# Power.net
KiCad netlist of a schematic drawn in Altium Designer
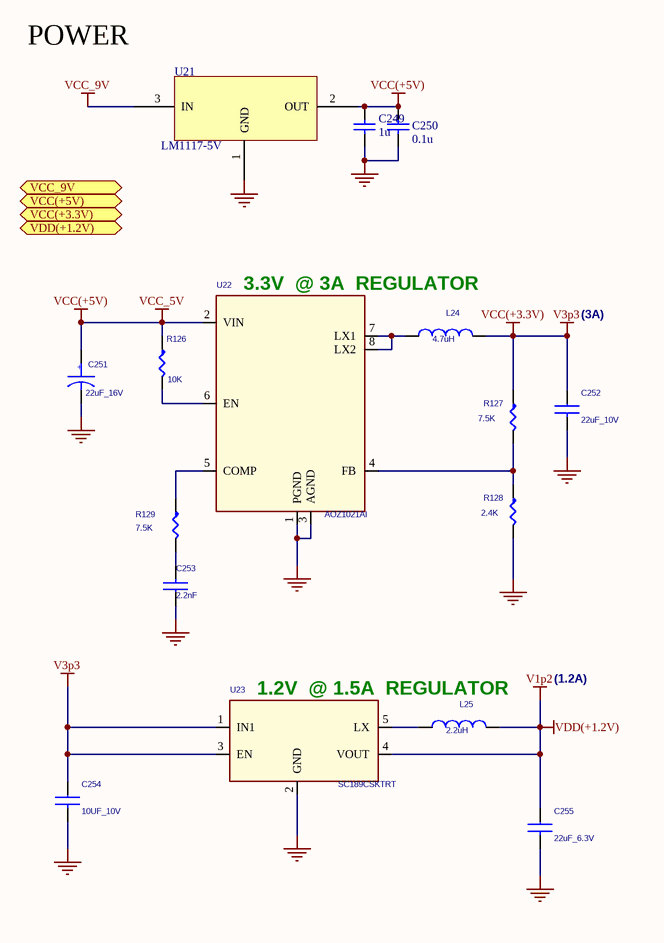
[diagram p0: Power.SchDoc]

(export (version "E")
  (design (tool "Eeschema 10.0.6"))
  (components
    (comp (ref "C249")
      (value "1u")
      (footprint "C0603")
      (description "50V/8.2u/0805")
      (fields (field (name "PUBLISHER") "Altium Limited"))
      (libsource (lib "Miscellaneous Devices") (part "Cap"))
    )
    (comp (ref "C250")
      (value "0.1u")
      (footprint "C0402")
      (description "Capacitor")
      (fields (field (name "PUBLISHER") "Altium Limited"))
      (libsource (lib "WM360") (part "CAP0805"))
    )
    (comp (ref "C251")
      (value "22uF_16V")
      (footprint "C0603")
      (description "CAP TANT 22UF 16V 10% 1206")
      (fields (field (name "MANUFACTURER") "Nichicon") (field (name "PART NUMBER") "F951C226KQAAQ2"))
      (libsource (lib "*") (part "CAP POL"))
    )
    (comp (ref "C252")
      (value "22uF_10V")
      (footprint "C0603")
      (libsource (lib "*") (part "CAPACITOR NON-POL"))
    )
    (comp (ref "C253")
      (value "2.2nF")
      (footprint "C0603")
      (description "CAP CER 2200PF 50V 10% X7R 0805")
      (fields (field (name "MANUFACTURER") "Yageo") (field (name "PART NUMBER") "CC0805KRX7R9BB222"))
      (libsource (lib "*") (part "CAPACITOR NON-POL"))
    )
    (comp (ref "C254")
      (value "10UF_10V")
      (footprint "C0603")
      (libsource (lib "*") (part "CAPACITOR NON-POL"))
    )
    (comp (ref "C255")
      (value "22uF_6.3V")
      (footprint "C0603")
      (libsource (lib "*") (part "CAPACITOR NON-POL"))
    )
    (comp (ref "L24")
      (value "4.7uH")
      (footprint "L0603")
      (description "INDUCTOR 4.7UH 2.7A 20% SMD")
      (fields (field (name "PART NUMBER") "NR6028T4R7M") (field (name "MANUFACTURER") "Taiyo Yuden"))
      (libsource (lib "*") (part "INDUCTOR"))
    )
    (comp (ref "L25")
      (value "2.2uH")
      (footprint "L0603")
      (description "INDUCTOR 2.2UH 1.20A 20% 1210")
      (fields (field (name "PART NUMBER") "NLCV32T-2R2M-PFR") (field (name "MANUFACTURER") "TDK Corporation"))
      (libsource (lib "*") (part "INDUCTOR"))
    )
    (comp (ref "R126")
      (value "10K")
      (footprint "0603S-RES")
      (description "RES 10.0K OHM 1/10W 1% 0603 SMD")
      (fields (field (name "MANUFACTURER") "Panasonic - ECG") (field (name "PART NUMBER") "ERJ-3EKF1002V"))
      (libsource (lib "*") (part "R_Dup1"))
    )
    (comp (ref "R127")
      (value "7.5K")
      (footprint "0603S-RES")
      (description "RES 7.5K OHM 1/10W 1% 0603 SMD")
      (fields (field (name "MANUFACTURER") "Panasonic - ECG") (field (name "PART NUMBER") "ERJ-3EKF7501V"))
      (libsource (lib "*") (part "R_Dup1"))
    )
    (comp (ref "R128")
      (value "2.4K")
      (footprint "0603S-RES")
      (description "RES 2.4K OHM 1/10W 1% 0603 SMD")
      (fields (field (name "MANUFACTURER") "Panasonic - ECG") (field (name "PART NUMBER") "ERJ-3EKF2401V"))
      (libsource (lib "*") (part "R_Dup1"))
    )
    (comp (ref "R129")
      (value "7.5K")
      (footprint "0603S-RES")
      (description "RES 7.5K OHM 1/10W 1% 0603 SMD")
      (fields (field (name "PART NUMBER") "ERJ-3EKF7501V") (field (name "MANUFACTURER") "Panasonic - ECG"))
      (libsource (lib "*") (part "R_Dup1"))
    )
    (comp (ref "U21") (value "LM1117-5V") (footprint "SOT-223") (libsource (lib "rs232") (part "AMS1117")))
    (comp (ref "U22")
      (value "AOZ1021AI")
      (footprint "SOIC127P600X175-8M")
      (description "IC REG BUCK SYNC ADJ 3A 8SOIC")
      (fields (field (name "MANUFACTURER") "Alpha & Omega Semiconductor Inc"))
      (libsource (lib "*") (part "AOZ1021AI"))
    )
    (comp (ref "U23")
      (value "SC189CSKTRT")
      (footprint "SOT95P280X145-5M")
      (description "IC REG BUCK SYNC 1.2V SOT23-5")
      (fields (field (name "MANUFACTURER") "Semtech"))
      (libsource (lib "*") (part "SC189CSKTRT"))
    )
  )
  (nets
    (net (code "1") (name "GND") (class "Default")
      (node (ref "C249") (pin "1") (pinfunction "1_1") (pintype "passive"))
      (node (ref "C250") (pin "2") (pinfunction "2_2") (pintype "passive"))
      (node (ref "C251") (pin "2") (pinfunction "2_2") (pintype "passive"))
      (node (ref "C252") (pin "2") (pinfunction "2_2") (pintype "passive"))
      (node (ref "C253") (pin "1") (pinfunction "1_1") (pintype "passive"))
      (node (ref "C254") (pin "2") (pinfunction "2_2") (pintype "passive"))
      (node (ref "C255") (pin "2") (pinfunction "2_2") (pintype "passive"))
      (node (ref "R128") (pin "2") (pinfunction "2_2") (pintype "passive"))
      (node (ref "U21") (pin "1") (pinfunction "GND_1") (pintype "passive"))
      (node (ref "U22") (pin "1") (pinfunction "PGND_1") (pintype "passive"))
      (node (ref "U22") (pin "3") (pinfunction "AGND_3") (pintype "passive"))
      (node (ref "U23") (pin "2") (pinfunction "GND_2") (pintype "passive"))
    )
    (net (code "2") (name "Net-(C253-Pad2)") (class "Default")
      (node (ref "C253") (pin "2") (pinfunction "2_2") (pintype "passive"))
      (node (ref "R129") (pin "2") (pinfunction "2_2") (pintype "passive"))
    )
    (net (code "3") (name "Net-(U22-COMP)") (class "Default")
      (node (ref "R129") (pin "1") (pinfunction "1_1") (pintype "passive"))
      (node (ref "U22") (pin "5") (pinfunction "COMP_5") (pintype "passive"))
    )
    (net (code "4") (name "Net-(U22-EN)") (class "Default")
      (node (ref "R126") (pin "2") (pinfunction "2_2") (pintype "passive"))
      (node (ref "U22") (pin "6") (pinfunction "EN_6") (pintype "passive"))
    )
    (net (code "5") (name "Net-(U22-FB)") (class "Default")
      (node (ref "R127") (pin "2") (pinfunction "2_2") (pintype "passive"))
      (node (ref "R128") (pin "1") (pinfunction "1_1") (pintype "passive"))
      (node (ref "U22") (pin "4") (pinfunction "FB_4") (pintype "passive"))
    )
    (net (code "6") (name "Net-(U22-LX1)") (class "Default")
      (node (ref "L24") (pin "1") (pinfunction "1_1") (pintype "passive"))
      (node (ref "U22") (pin "7") (pinfunction "LX1_7") (pintype "passive"))
      (node (ref "U22") (pin "8") (pinfunction "LX2_8") (pintype "passive"))
    )
    (net (code "7") (name "Net-(U23-LX)") (class "Default")
      (node (ref "L25") (pin "1") (pinfunction "1_1") (pintype "passive"))
      (node (ref "U23") (pin "5") (pinfunction "LX_5") (pintype "passive"))
    )
    (net (code "8") (name "V1p2") (class "Default")
      (node (ref "C255") (pin "1") (pinfunction "1_1") (pintype "passive"))
      (node (ref "L25") (pin "2") (pinfunction "2_2") (pintype "passive"))
      (node (ref "U23") (pin "4") (pinfunction "VOUT_4") (pintype "passive"))
    )
    (net (code "9") (name "V3p3") (class "Default")
      (node (ref "C252") (pin "1") (pinfunction "1_1") (pintype "passive"))
      (node (ref "C254") (pin "1") (pinfunction "1_1") (pintype "passive"))
      (node (ref "L24") (pin "2") (pinfunction "2_2") (pintype "passive"))
      (node (ref "R127") (pin "1") (pinfunction "1_1") (pintype "passive"))
      (node (ref "U23") (pin "1") (pinfunction "IN1_1") (pintype "passive"))
      (node (ref "U23") (pin "3") (pinfunction "EN_3") (pintype "passive"))
    )
    (net (code "10") (name "VCC(+5V)") (class "Default")
      (node (ref "C249") (pin "2") (pinfunction "2_2") (pintype "passive"))
      (node (ref "C250") (pin "1") (pinfunction "1_1") (pintype "passive"))
      (node (ref "C251") (pin "1") (pinfunction "1_1") (pintype "passive"))
      (node (ref "R126") (pin "1") (pinfunction "1_1") (pintype "passive"))
      (node (ref "U21") (pin "2") (pinfunction "OUT_2") (pintype "passive"))
      (node (ref "U22") (pin "2") (pinfunction "VIN_2") (pintype "passive"))
    )
    (net (code "11") (name "VCC_9V") (class "Default")
      (node (ref "U21") (pin "3") (pinfunction "IN_3") (pintype "passive"))
    )
  )
)
